# motorcomp.net
KiCad netlist of a schematic drawn in EAGLE
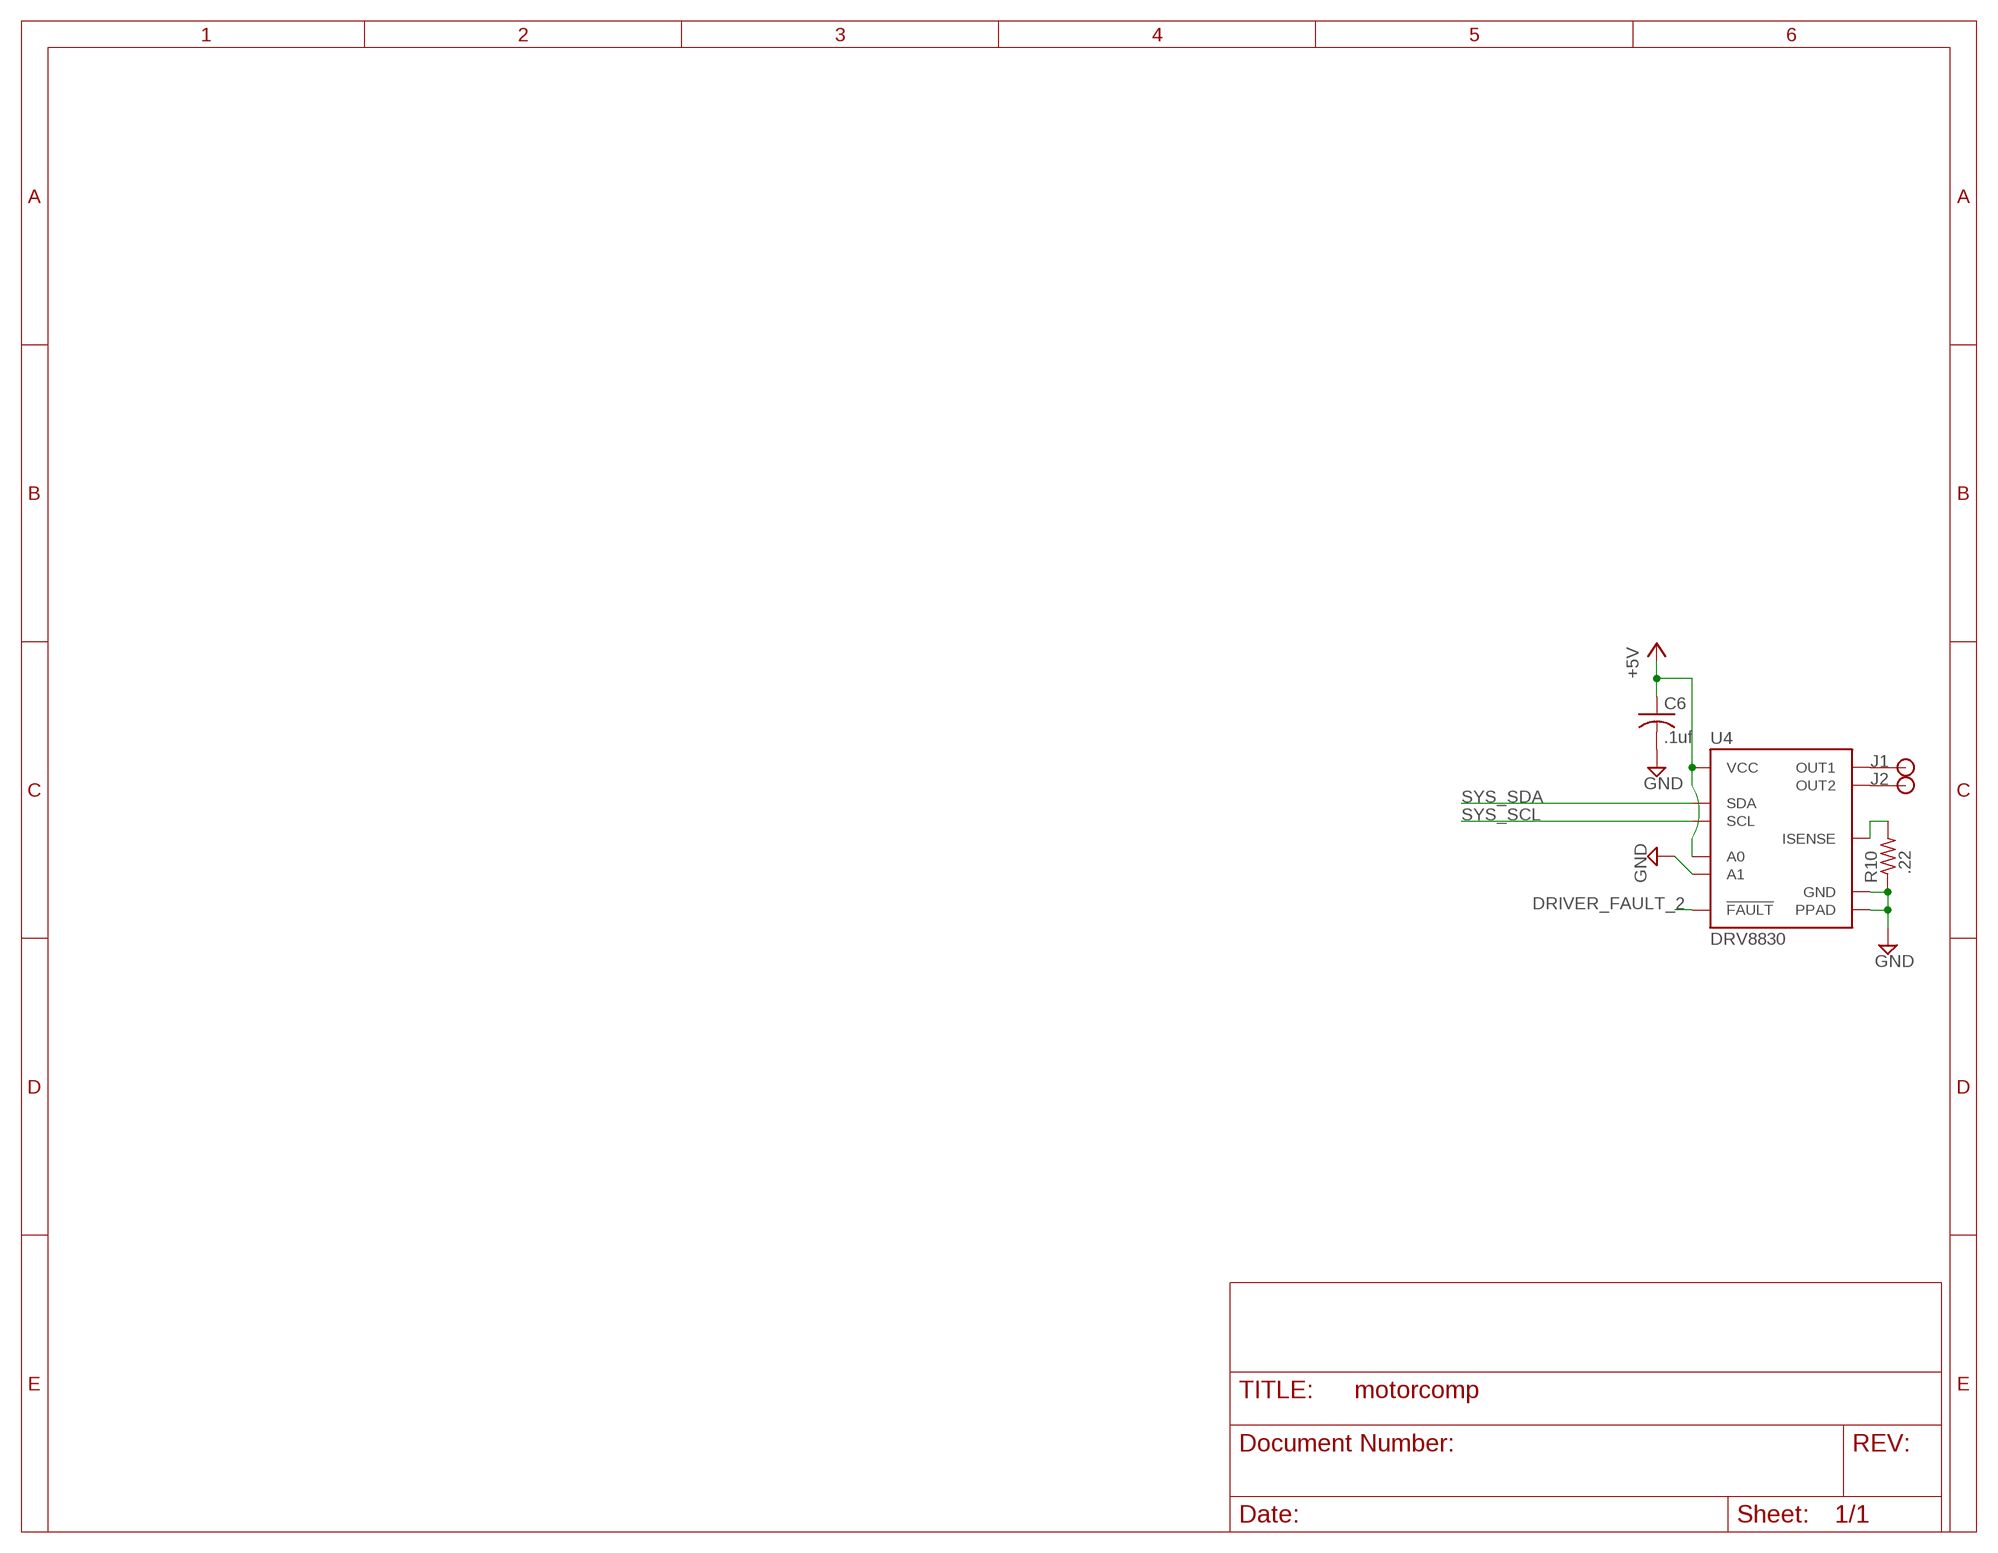
[diagram p0: schematic, sheet 1]

(export (version "E")
  (design (tool "Eeschema 10.0.6"))
  (components
    (comp (ref "C6")
      (value ".1uf")
      (footprint "eagle-import:C0603")
      (libsource (lib "eagle-import") (part "C-USC0603"))
    )
    (comp (ref "J1")
      (value "2MMPAD")
      (footprint "eagle-import:2MMPAD")
      (libsource (lib "eagle-import") (part "2MMPAD"))
    )
    (comp (ref "J2")
      (value "2MMPAD")
      (footprint "eagle-import:2MMPAD")
      (libsource (lib "eagle-import") (part "2MMPAD"))
    )
    (comp (ref "R10")
      (value ".22")
      (footprint "eagle-import:R0402")
      (libsource (lib "eagle-import") (part "R-US_R0402"))
    )
    (comp (ref "U4")
      (value "DRV8830")
      (footprint "eagle-import:MSOP-10-GNDPAD")
      (libsource (lib "eagle-import") (part "DRV8830"))
    )
  )
  (nets
    (net (code "1") (name "+5V") (class "Default")
      (node (ref "C6") (pin "1") (pinfunction "1_1") (pintype "passive"))
      (node (ref "U4") (pin "4") (pinfunction "VCC_4") (pintype "power_in"))
      (node (ref "U4") (pin "7") (pinfunction "A0_7") (pintype "input"))
    )
    (net (code "2") (name "/DRIVER_FAULT_2") (class "Default")
      (node (ref "U4") (pin "6") (pinfunction "~{FAULT}_6") (pintype "output"))
    )
    (net (code "3") (name "/SYS_SCL") (class "Default")
      (node (ref "U4") (pin "10") (pinfunction "SCL_10") (pintype "input"))
    )
    (net (code "4") (name "/SYS_SDA") (class "Default")
      (node (ref "U4") (pin "9") (pinfunction "SDA_9") (pintype "bidirectional"))
    )
    (net (code "5") (name "GND") (class "Default")
      (node (ref "C6") (pin "2") (pinfunction "2_2") (pintype "passive"))
      (node (ref "R10") (pin "1") (pinfunction "1_1") (pintype "passive"))
      (node (ref "U4") (pin "5") (pinfunction "GND_5") (pintype "power_in"))
      (node (ref "U4") (pin "8") (pinfunction "A1_8") (pintype "input"))
      (node (ref "U4") (pin "GND") (pinfunction "PPAD_GND") (pintype "power_in"))
    )
    (net (code "6") (name "Net-(U4-ISENSE)") (class "Default")
      (node (ref "R10") (pin "2") (pinfunction "2_2") (pintype "passive"))
      (node (ref "U4") (pin "2") (pinfunction "ISENSE_2") (pintype "bidirectional"))
    )
    (net (code "7") (name "Net-(U4-OUT1)") (class "Default")
      (node (ref "J1") (pin "P$1") (pinfunction "P$1_P$1") (pintype "bidirectional"))
      (node (ref "U4") (pin "3") (pinfunction "OUT1_3") (pintype "power_in"))
    )
    (net (code "8") (name "Net-(U4-OUT2)") (class "Default")
      (node (ref "J2") (pin "P$1") (pinfunction "P$1_P$1") (pintype "bidirectional"))
      (node (ref "U4") (pin "1") (pinfunction "OUT2_1") (pintype "power_in"))
    )
  )
)
